# keypad-encoder.net
KiCad netlist of a schematic drawn in EAGLE
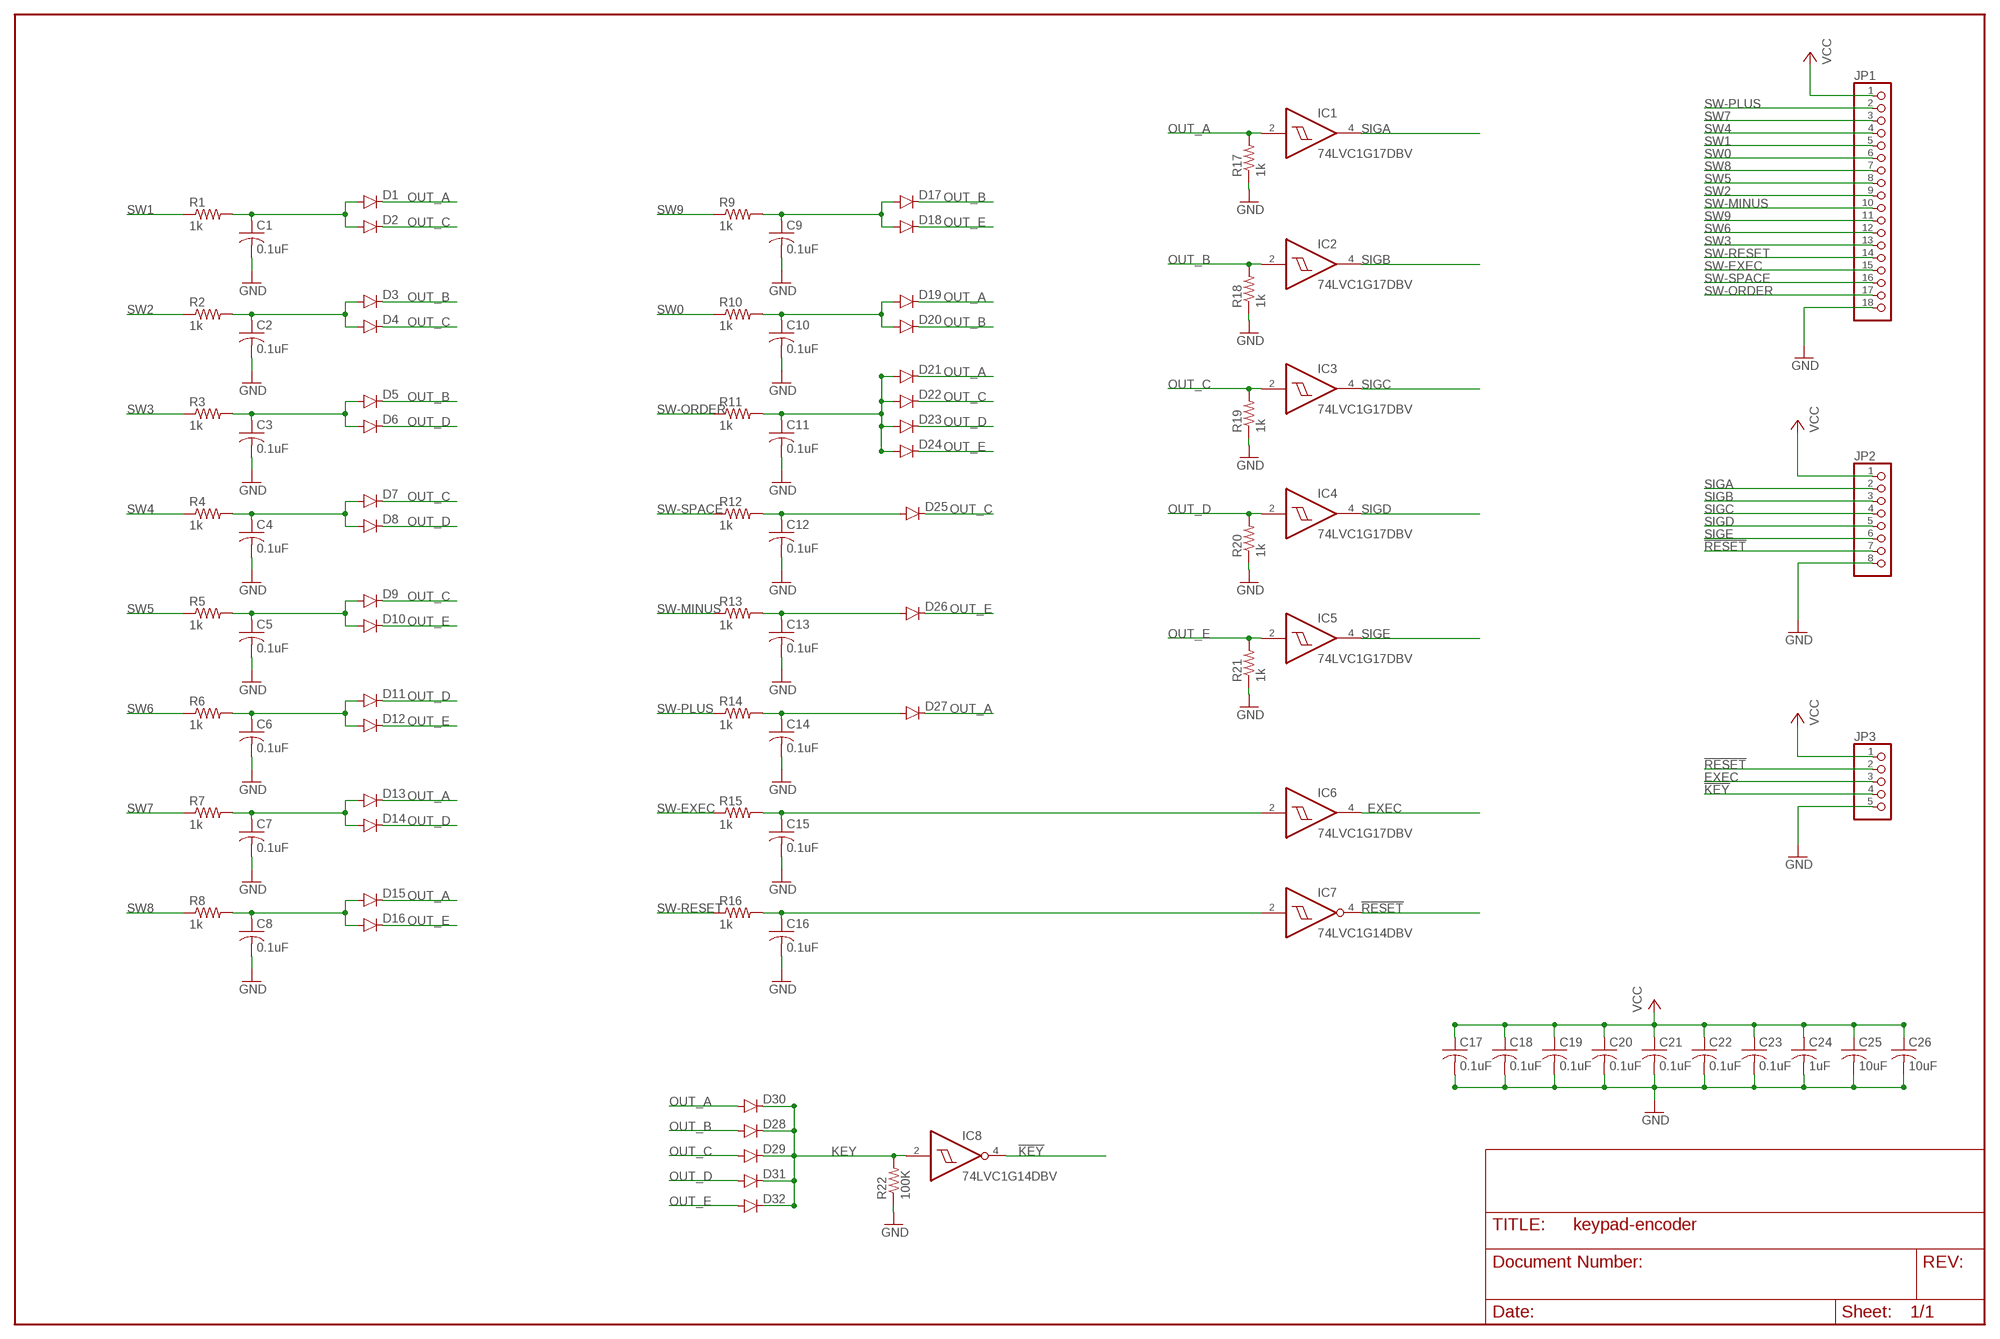
[diagram p0: schematic, sheet 1]

(export (version "E")
  (design (tool "Eeschema 10.0.6"))
  (components
    (comp (ref "C1")
      (value "0.1uF")
      (footprint "eagle-import:C0805")
      (libsource (lib "eagle-import") (part "C-USC0805"))
    )
    (comp (ref "C2")
      (value "0.1uF")
      (footprint "eagle-import:C0805")
      (libsource (lib "eagle-import") (part "C-USC0805"))
    )
    (comp (ref "C3")
      (value "0.1uF")
      (footprint "eagle-import:C0805")
      (libsource (lib "eagle-import") (part "C-USC0805"))
    )
    (comp (ref "C4")
      (value "0.1uF")
      (footprint "eagle-import:C0805")
      (libsource (lib "eagle-import") (part "C-USC0805"))
    )
    (comp (ref "C5")
      (value "0.1uF")
      (footprint "eagle-import:C0805")
      (libsource (lib "eagle-import") (part "C-USC0805"))
    )
    (comp (ref "C6")
      (value "0.1uF")
      (footprint "eagle-import:C0805")
      (libsource (lib "eagle-import") (part "C-USC0805"))
    )
    (comp (ref "C7")
      (value "0.1uF")
      (footprint "eagle-import:C0805")
      (libsource (lib "eagle-import") (part "C-USC0805"))
    )
    (comp (ref "C8")
      (value "0.1uF")
      (footprint "eagle-import:C0805")
      (libsource (lib "eagle-import") (part "C-USC0805"))
    )
    (comp (ref "C9")
      (value "0.1uF")
      (footprint "eagle-import:C0805")
      (libsource (lib "eagle-import") (part "C-USC0805"))
    )
    (comp (ref "C10")
      (value "0.1uF")
      (footprint "eagle-import:C0805")
      (libsource (lib "eagle-import") (part "C-USC0805"))
    )
    (comp (ref "C11")
      (value "0.1uF")
      (footprint "eagle-import:C0805")
      (libsource (lib "eagle-import") (part "C-USC0805"))
    )
    (comp (ref "C12")
      (value "0.1uF")
      (footprint "eagle-import:C0805")
      (libsource (lib "eagle-import") (part "C-USC0805"))
    )
    (comp (ref "C13")
      (value "0.1uF")
      (footprint "eagle-import:C0805")
      (libsource (lib "eagle-import") (part "C-USC0805"))
    )
    (comp (ref "C14")
      (value "0.1uF")
      (footprint "eagle-import:C0805")
      (libsource (lib "eagle-import") (part "C-USC0805"))
    )
    (comp (ref "C15")
      (value "0.1uF")
      (footprint "eagle-import:C0805")
      (libsource (lib "eagle-import") (part "C-USC0805"))
    )
    (comp (ref "C16")
      (value "0.1uF")
      (footprint "eagle-import:C0805")
      (libsource (lib "eagle-import") (part "C-USC0805"))
    )
    (comp (ref "C17")
      (value "0.1uF")
      (footprint "eagle-import:C0805")
      (libsource (lib "eagle-import") (part "C-USC0805"))
    )
    (comp (ref "C18")
      (value "0.1uF")
      (footprint "eagle-import:C0805")
      (libsource (lib "eagle-import") (part "C-USC0805"))
    )
    (comp (ref "C19")
      (value "0.1uF")
      (footprint "eagle-import:C0805")
      (libsource (lib "eagle-import") (part "C-USC0805"))
    )
    (comp (ref "C20")
      (value "0.1uF")
      (footprint "eagle-import:C0805")
      (libsource (lib "eagle-import") (part "C-USC0805"))
    )
    (comp (ref "C21")
      (value "0.1uF")
      (footprint "eagle-import:C0805")
      (libsource (lib "eagle-import") (part "C-USC0805"))
    )
    (comp (ref "C22")
      (value "0.1uF")
      (footprint "eagle-import:C0805")
      (libsource (lib "eagle-import") (part "C-USC0805"))
    )
    (comp (ref "C23")
      (value "0.1uF")
      (footprint "eagle-import:C0805")
      (libsource (lib "eagle-import") (part "C-USC0805"))
    )
    (comp (ref "C24")
      (value "1uF")
      (footprint "eagle-import:C0805")
      (libsource (lib "eagle-import") (part "C-USC0805"))
    )
    (comp (ref "C25")
      (value "10uF")
      (footprint "eagle-import:C0805")
      (libsource (lib "eagle-import") (part "C-USC0805"))
    )
    (comp (ref "C26")
      (value "10uF")
      (footprint "eagle-import:C0805")
      (libsource (lib "eagle-import") (part "C-USC0805"))
    )
    (comp (ref "D1")
      (value "DIODEPTH")
      (footprint "eagle-import:DIODE-1N4001")
      (libsource (lib "eagle-import") (part "DIODEPTH"))
    )
    (comp (ref "D2")
      (value "DIODEPTH")
      (footprint "eagle-import:DIODE-1N4001")
      (libsource (lib "eagle-import") (part "DIODEPTH"))
    )
    (comp (ref "D3")
      (value "DIODEPTH")
      (footprint "eagle-import:DIODE-1N4001")
      (libsource (lib "eagle-import") (part "DIODEPTH"))
    )
    (comp (ref "D4")
      (value "DIODEPTH")
      (footprint "eagle-import:DIODE-1N4001")
      (libsource (lib "eagle-import") (part "DIODEPTH"))
    )
    (comp (ref "D5")
      (value "DIODEPTH")
      (footprint "eagle-import:DIODE-1N4001")
      (libsource (lib "eagle-import") (part "DIODEPTH"))
    )
    (comp (ref "D6")
      (value "DIODEPTH")
      (footprint "eagle-import:DIODE-1N4001")
      (libsource (lib "eagle-import") (part "DIODEPTH"))
    )
    (comp (ref "D7")
      (value "DIODEPTH")
      (footprint "eagle-import:DIODE-1N4001")
      (libsource (lib "eagle-import") (part "DIODEPTH"))
    )
    (comp (ref "D8")
      (value "DIODEPTH")
      (footprint "eagle-import:DIODE-1N4001")
      (libsource (lib "eagle-import") (part "DIODEPTH"))
    )
    (comp (ref "D9")
      (value "DIODEPTH")
      (footprint "eagle-import:DIODE-1N4001")
      (libsource (lib "eagle-import") (part "DIODEPTH"))
    )
    (comp (ref "D10")
      (value "DIODEPTH")
      (footprint "eagle-import:DIODE-1N4001")
      (libsource (lib "eagle-import") (part "DIODEPTH"))
    )
    (comp (ref "D11")
      (value "DIODEPTH")
      (footprint "eagle-import:DIODE-1N4001")
      (libsource (lib "eagle-import") (part "DIODEPTH"))
    )
    (comp (ref "D12")
      (value "DIODEPTH")
      (footprint "eagle-import:DIODE-1N4001")
      (libsource (lib "eagle-import") (part "DIODEPTH"))
    )
    (comp (ref "D13")
      (value "DIODEPTH")
      (footprint "eagle-import:DIODE-1N4001")
      (libsource (lib "eagle-import") (part "DIODEPTH"))
    )
    (comp (ref "D14")
      (value "DIODEPTH")
      (footprint "eagle-import:DIODE-1N4001")
      (libsource (lib "eagle-import") (part "DIODEPTH"))
    )
    (comp (ref "D15")
      (value "DIODEPTH")
      (footprint "eagle-import:DIODE-1N4001")
      (libsource (lib "eagle-import") (part "DIODEPTH"))
    )
    (comp (ref "D16")
      (value "DIODEPTH")
      (footprint "eagle-import:DIODE-1N4001")
      (libsource (lib "eagle-import") (part "DIODEPTH"))
    )
    (comp (ref "D17")
      (value "DIODEPTH")
      (footprint "eagle-import:DIODE-1N4001")
      (libsource (lib "eagle-import") (part "DIODEPTH"))
    )
    (comp (ref "D18")
      (value "DIODEPTH")
      (footprint "eagle-import:DIODE-1N4001")
      (libsource (lib "eagle-import") (part "DIODEPTH"))
    )
    (comp (ref "D19")
      (value "DIODEPTH")
      (footprint "eagle-import:DIODE-1N4001")
      (libsource (lib "eagle-import") (part "DIODEPTH"))
    )
    (comp (ref "D20")
      (value "DIODEPTH")
      (footprint "eagle-import:DIODE-1N4001")
      (libsource (lib "eagle-import") (part "DIODEPTH"))
    )
    (comp (ref "D21")
      (value "DIODEPTH")
      (footprint "eagle-import:DIODE-1N4001")
      (libsource (lib "eagle-import") (part "DIODEPTH"))
    )
    (comp (ref "D22")
      (value "DIODEPTH")
      (footprint "eagle-import:DIODE-1N4001")
      (libsource (lib "eagle-import") (part "DIODEPTH"))
    )
    (comp (ref "D23")
      (value "DIODEPTH")
      (footprint "eagle-import:DIODE-1N4001")
      (libsource (lib "eagle-import") (part "DIODEPTH"))
    )
    (comp (ref "D24")
      (value "DIODEPTH")
      (footprint "eagle-import:DIODE-1N4001")
      (libsource (lib "eagle-import") (part "DIODEPTH"))
    )
    (comp (ref "D25")
      (value "DIODEPTH")
      (footprint "eagle-import:DIODE-1N4001")
      (libsource (lib "eagle-import") (part "DIODEPTH"))
    )
    (comp (ref "D26")
      (value "DIODEPTH")
      (footprint "eagle-import:DIODE-1N4001")
      (libsource (lib "eagle-import") (part "DIODEPTH"))
    )
    (comp (ref "D27")
      (value "DIODEPTH")
      (footprint "eagle-import:DIODE-1N4001")
      (libsource (lib "eagle-import") (part "DIODEPTH"))
    )
    (comp (ref "D28")
      (value "DIODEPTH")
      (footprint "eagle-import:DIODE-1N4001")
      (libsource (lib "eagle-import") (part "DIODEPTH"))
    )
    (comp (ref "D29")
      (value "DIODEPTH")
      (footprint "eagle-import:DIODE-1N4001")
      (libsource (lib "eagle-import") (part "DIODEPTH"))
    )
    (comp (ref "D30")
      (value "DIODEPTH")
      (footprint "eagle-import:DIODE-1N4001")
      (libsource (lib "eagle-import") (part "DIODEPTH"))
    )
    (comp (ref "D31")
      (value "DIODEPTH")
      (footprint "eagle-import:DIODE-1N4001")
      (libsource (lib "eagle-import") (part "DIODEPTH"))
    )
    (comp (ref "D32")
      (value "DIODEPTH")
      (footprint "eagle-import:DIODE-1N4001")
      (libsource (lib "eagle-import") (part "DIODEPTH"))
    )
    (comp (ref "IC1")
      (value "74LVC1G17DBV")
      (footprint "eagle-import:SOT23-5")
      (libsource (lib "eagle-import") (part "741G17DBVLVC"))
    )
    (comp (ref "IC2")
      (value "74LVC1G17DBV")
      (footprint "eagle-import:SOT23-5")
      (libsource (lib "eagle-import") (part "741G17DBVLVC"))
    )
    (comp (ref "IC3")
      (value "74LVC1G17DBV")
      (footprint "eagle-import:SOT23-5")
      (libsource (lib "eagle-import") (part "741G17DBVLVC"))
    )
    (comp (ref "IC4")
      (value "74LVC1G17DBV")
      (footprint "eagle-import:SOT23-5")
      (libsource (lib "eagle-import") (part "741G17DBVLVC"))
    )
    (comp (ref "IC5")
      (value "74LVC1G17DBV")
      (footprint "eagle-import:SOT23-5")
      (libsource (lib "eagle-import") (part "741G17DBVLVC"))
    )
    (comp (ref "IC6")
      (value "74LVC1G17DBV")
      (footprint "eagle-import:SOT23-5")
      (libsource (lib "eagle-import") (part "741G17DBVLVC"))
    )
    (comp (ref "IC7")
      (value "74LVC1G14DBV")
      (footprint "eagle-import:SOT23-5")
      (libsource (lib "eagle-import") (part "741G14DBVLVC"))
    )
    (comp (ref "IC8")
      (value "74LVC1G14DBV")
      (footprint "eagle-import:SOT23-5")
      (libsource (lib "eagle-import") (part "741G14DBVLVC"))
    )
    (comp (ref "JP1")
      (value "PINHD-1X18")
      (footprint "eagle-import:1X18")
      (libsource (lib "eagle-import") (part "PINHD-1X18"))
    )
    (comp (ref "JP2")
      (value "PINHD-1X8")
      (footprint "eagle-import:1X08")
      (libsource (lib "eagle-import") (part "PINHD-1X8"))
    )
    (comp (ref "JP3")
      (value "PINHD-1X5")
      (footprint "eagle-import:1X05")
      (libsource (lib "eagle-import") (part "PINHD-1X5"))
    )
    (comp (ref "R1")
      (value "1k")
      (footprint "eagle-import:R0805")
      (libsource (lib "eagle-import") (part "R-US_R0805"))
    )
    (comp (ref "R2")
      (value "1k")
      (footprint "eagle-import:R0805")
      (libsource (lib "eagle-import") (part "R-US_R0805"))
    )
    (comp (ref "R3")
      (value "1k")
      (footprint "eagle-import:R0805")
      (libsource (lib "eagle-import") (part "R-US_R0805"))
    )
    (comp (ref "R4")
      (value "1k")
      (footprint "eagle-import:R0805")
      (libsource (lib "eagle-import") (part "R-US_R0805"))
    )
    (comp (ref "R5")
      (value "1k")
      (footprint "eagle-import:R0805")
      (libsource (lib "eagle-import") (part "R-US_R0805"))
    )
    (comp (ref "R6")
      (value "1k")
      (footprint "eagle-import:R0805")
      (libsource (lib "eagle-import") (part "R-US_R0805"))
    )
    (comp (ref "R7")
      (value "1k")
      (footprint "eagle-import:R0805")
      (libsource (lib "eagle-import") (part "R-US_R0805"))
    )
    (comp (ref "R8")
      (value "1k")
      (footprint "eagle-import:R0805")
      (libsource (lib "eagle-import") (part "R-US_R0805"))
    )
    (comp (ref "R9")
      (value "1k")
      (footprint "eagle-import:R0805")
      (libsource (lib "eagle-import") (part "R-US_R0805"))
    )
    (comp (ref "R10")
      (value "1k")
      (footprint "eagle-import:R0805")
      (libsource (lib "eagle-import") (part "R-US_R0805"))
    )
    (comp (ref "R11")
      (value "1k")
      (footprint "eagle-import:R0805")
      (libsource (lib "eagle-import") (part "R-US_R0805"))
    )
    (comp (ref "R12")
      (value "1k")
      (footprint "eagle-import:R0805")
      (libsource (lib "eagle-import") (part "R-US_R0805"))
    )
    (comp (ref "R13")
      (value "1k")
      (footprint "eagle-import:R0805")
      (libsource (lib "eagle-import") (part "R-US_R0805"))
    )
    (comp (ref "R14")
      (value "1k")
      (footprint "eagle-import:R0805")
      (libsource (lib "eagle-import") (part "R-US_R0805"))
    )
    (comp (ref "R15")
      (value "1k")
      (footprint "eagle-import:R0805")
      (libsource (lib "eagle-import") (part "R-US_R0805"))
    )
    (comp (ref "R16")
      (value "1k")
      (footprint "eagle-import:R0805")
      (libsource (lib "eagle-import") (part "R-US_R0805"))
    )
    (comp (ref "R17")
      (value "1k")
      (footprint "eagle-import:R0805")
      (libsource (lib "eagle-import") (part "R-US_R0805"))
    )
    (comp (ref "R18")
      (value "1k")
      (footprint "eagle-import:R0805")
      (libsource (lib "eagle-import") (part "R-US_R0805"))
    )
    (comp (ref "R19")
      (value "1k")
      (footprint "eagle-import:R0805")
      (libsource (lib "eagle-import") (part "R-US_R0805"))
    )
    (comp (ref "R20")
      (value "1k")
      (footprint "eagle-import:R0805")
      (libsource (lib "eagle-import") (part "R-US_R0805"))
    )
    (comp (ref "R21")
      (value "1k")
      (footprint "eagle-import:R0805")
      (libsource (lib "eagle-import") (part "R-US_R0805"))
    )
    (comp (ref "R22")
      (value "100K")
      (footprint "eagle-import:R0805")
      (libsource (lib "eagle-import") (part "R-US_R0805"))
    )
  )
  (nets
    (net (code "1") (name "/EXEC") (class "Default")
      (node (ref "IC6") (pin "4") (pinfunction "O_4") (pintype "output"))
      (node (ref "JP3") (pin "3") (pinfunction "3_3") (pintype "passive"))
    )
    (net (code "2") (name "/KEY") (class "Default")
      (node (ref "D28") (pin "C") (pinfunction "C_C") (pintype "passive"))
      (node (ref "D29") (pin "C") (pinfunction "C_C") (pintype "passive"))
      (node (ref "D30") (pin "C") (pinfunction "C_C") (pintype "passive"))
      (node (ref "D31") (pin "C") (pinfunction "C_C") (pintype "passive"))
      (node (ref "D32") (pin "C") (pinfunction "C_C") (pintype "passive"))
      (node (ref "IC8") (pin "2") (pinfunction "I_2") (pintype "input"))
      (node (ref "R22") (pin "2") (pinfunction "2_2") (pintype "passive"))
    )
    (net (code "3") (name "/OUT_A") (class "Default")
      (node (ref "D1") (pin "C") (pinfunction "C_C") (pintype "passive"))
      (node (ref "D13") (pin "C") (pinfunction "C_C") (pintype "passive"))
      (node (ref "D15") (pin "C") (pinfunction "C_C") (pintype "passive"))
      (node (ref "D19") (pin "C") (pinfunction "C_C") (pintype "passive"))
      (node (ref "D21") (pin "C") (pinfunction "C_C") (pintype "passive"))
      (node (ref "D27") (pin "C") (pinfunction "C_C") (pintype "passive"))
      (node (ref "D30") (pin "A") (pinfunction "A_A") (pintype "passive"))
      (node (ref "IC1") (pin "2") (pinfunction "I_2") (pintype "input"))
      (node (ref "R17") (pin "2") (pinfunction "2_2") (pintype "passive"))
    )
    (net (code "4") (name "/OUT_B") (class "Default")
      (node (ref "D17") (pin "C") (pinfunction "C_C") (pintype "passive"))
      (node (ref "D20") (pin "C") (pinfunction "C_C") (pintype "passive"))
      (node (ref "D28") (pin "A") (pinfunction "A_A") (pintype "passive"))
      (node (ref "D3") (pin "C") (pinfunction "C_C") (pintype "passive"))
      (node (ref "D5") (pin "C") (pinfunction "C_C") (pintype "passive"))
      (node (ref "IC2") (pin "2") (pinfunction "I_2") (pintype "input"))
      (node (ref "R18") (pin "2") (pinfunction "2_2") (pintype "passive"))
    )
    (net (code "5") (name "/OUT_C") (class "Default")
      (node (ref "D2") (pin "C") (pinfunction "C_C") (pintype "passive"))
      (node (ref "D22") (pin "C") (pinfunction "C_C") (pintype "passive"))
      (node (ref "D25") (pin "C") (pinfunction "C_C") (pintype "passive"))
      (node (ref "D29") (pin "A") (pinfunction "A_A") (pintype "passive"))
      (node (ref "D4") (pin "C") (pinfunction "C_C") (pintype "passive"))
      (node (ref "D7") (pin "C") (pinfunction "C_C") (pintype "passive"))
      (node (ref "D9") (pin "C") (pinfunction "C_C") (pintype "passive"))
      (node (ref "IC3") (pin "2") (pinfunction "I_2") (pintype "input"))
      (node (ref "R19") (pin "2") (pinfunction "2_2") (pintype "passive"))
    )
    (net (code "6") (name "/OUT_D") (class "Default")
      (node (ref "D11") (pin "C") (pinfunction "C_C") (pintype "passive"))
      (node (ref "D14") (pin "C") (pinfunction "C_C") (pintype "passive"))
      (node (ref "D23") (pin "C") (pinfunction "C_C") (pintype "passive"))
      (node (ref "D31") (pin "A") (pinfunction "A_A") (pintype "passive"))
      (node (ref "D6") (pin "C") (pinfunction "C_C") (pintype "passive"))
      (node (ref "D8") (pin "C") (pinfunction "C_C") (pintype "passive"))
      (node (ref "IC4") (pin "2") (pinfunction "I_2") (pintype "input"))
      (node (ref "R20") (pin "2") (pinfunction "2_2") (pintype "passive"))
    )
    (net (code "7") (name "/OUT_E") (class "Default")
      (node (ref "D10") (pin "C") (pinfunction "C_C") (pintype "passive"))
      (node (ref "D12") (pin "C") (pinfunction "C_C") (pintype "passive"))
      (node (ref "D16") (pin "C") (pinfunction "C_C") (pintype "passive"))
      (node (ref "D18") (pin "C") (pinfunction "C_C") (pintype "passive"))
      (node (ref "D24") (pin "C") (pinfunction "C_C") (pintype "passive"))
      (node (ref "D26") (pin "C") (pinfunction "C_C") (pintype "passive"))
      (node (ref "D32") (pin "A") (pinfunction "A_A") (pintype "passive"))
      (node (ref "IC5") (pin "2") (pinfunction "I_2") (pintype "input"))
      (node (ref "R21") (pin "2") (pinfunction "2_2") (pintype "passive"))
    )
    (net (code "8") (name "/SIGA") (class "Default")
      (node (ref "IC1") (pin "4") (pinfunction "O_4") (pintype "output"))
      (node (ref "JP2") (pin "2") (pinfunction "2_2") (pintype "passive"))
    )
    (net (code "9") (name "/SIGB") (class "Default")
      (node (ref "IC2") (pin "4") (pinfunction "O_4") (pintype "output"))
      (node (ref "JP2") (pin "3") (pinfunction "3_3") (pintype "passive"))
    )
    (net (code "10") (name "/SIGC") (class "Default")
      (node (ref "IC3") (pin "4") (pinfunction "O_4") (pintype "output"))
      (node (ref "JP2") (pin "4") (pinfunction "4_4") (pintype "passive"))
    )
    (net (code "11") (name "/SIGD") (class "Default")
      (node (ref "IC4") (pin "4") (pinfunction "O_4") (pintype "output"))
      (node (ref "JP2") (pin "5") (pinfunction "5_5") (pintype "passive"))
    )
    (net (code "12") (name "/SIGE") (class "Default")
      (node (ref "IC5") (pin "4") (pinfunction "O_4") (pintype "output"))
      (node (ref "JP2") (pin "6") (pinfunction "6_6") (pintype "passive"))
    )
    (net (code "13") (name "/SW-EXEC") (class "Default")
      (node (ref "JP1") (pin "15") (pinfunction "15_15") (pintype "passive"))
      (node (ref "R15") (pin "1") (pinfunction "1_1") (pintype "passive"))
    )
    (net (code "14") (name "/SW-MINUS") (class "Default")
      (node (ref "JP1") (pin "10") (pinfunction "10_10") (pintype "passive"))
      (node (ref "R13") (pin "1") (pinfunction "1_1") (pintype "passive"))
    )
    (net (code "15") (name "/SW-ORDER") (class "Default")
      (node (ref "JP1") (pin "17") (pinfunction "17_17") (pintype "passive"))
      (node (ref "R11") (pin "1") (pinfunction "1_1") (pintype "passive"))
    )
    (net (code "16") (name "/SW-PLUS") (class "Default")
      (node (ref "JP1") (pin "2") (pinfunction "2_2") (pintype "passive"))
      (node (ref "R14") (pin "1") (pinfunction "1_1") (pintype "passive"))
    )
    (net (code "17") (name "/SW-RESET") (class "Default")
      (node (ref "JP1") (pin "14") (pinfunction "14_14") (pintype "passive"))
      (node (ref "R16") (pin "1") (pinfunction "1_1") (pintype "passive"))
    )
    (net (code "18") (name "/SW-SPACE") (class "Default")
      (node (ref "JP1") (pin "16") (pinfunction "16_16") (pintype "passive"))
      (node (ref "R12") (pin "1") (pinfunction "1_1") (pintype "passive"))
    )
    (net (code "19") (name "/SW0") (class "Default")
      (node (ref "JP1") (pin "6") (pinfunction "6_6") (pintype "passive"))
      (node (ref "R10") (pin "1") (pinfunction "1_1") (pintype "passive"))
    )
    (net (code "20") (name "/SW1") (class "Default")
      (node (ref "JP1") (pin "5") (pinfunction "5_5") (pintype "passive"))
      (node (ref "R1") (pin "1") (pinfunction "1_1") (pintype "passive"))
    )
    (net (code "21") (name "/SW2") (class "Default")
      (node (ref "JP1") (pin "9") (pinfunction "9_9") (pintype "passive"))
      (node (ref "R2") (pin "1") (pinfunction "1_1") (pintype "passive"))
    )
    (net (code "22") (name "/SW3") (class "Default")
      (node (ref "JP1") (pin "13") (pinfunction "13_13") (pintype "passive"))
      (node (ref "R3") (pin "1") (pinfunction "1_1") (pintype "passive"))
    )
    (net (code "23") (name "/SW4") (class "Default")
      (node (ref "JP1") (pin "4") (pinfunction "4_4") (pintype "passive"))
      (node (ref "R4") (pin "1") (pinfunction "1_1") (pintype "passive"))
    )
    (net (code "24") (name "/SW5") (class "Default")
      (node (ref "JP1") (pin "8") (pinfunction "8_8") (pintype "passive"))
      (node (ref "R5") (pin "1") (pinfunction "1_1") (pintype "passive"))
    )
    (net (code "25") (name "/SW6") (class "Default")
      (node (ref "JP1") (pin "12") (pinfunction "12_12") (pintype "passive"))
      (node (ref "R6") (pin "1") (pinfunction "1_1") (pintype "passive"))
    )
    (net (code "26") (name "/SW7") (class "Default")
      (node (ref "JP1") (pin "3") (pinfunction "3_3") (pintype "passive"))
      (node (ref "R7") (pin "1") (pinfunction "1_1") (pintype "passive"))
    )
    (net (code "27") (name "/SW8") (class "Default")
      (node (ref "JP1") (pin "7") (pinfunction "7_7") (pintype "passive"))
      (node (ref "R8") (pin "1") (pinfunction "1_1") (pintype "passive"))
    )
    (net (code "28") (name "/SW9") (class "Default")
      (node (ref "JP1") (pin "11") (pinfunction "11_11") (pintype "passive"))
      (node (ref "R9") (pin "1") (pinfunction "1_1") (pintype "passive"))
    )
    (net (code "29") (name "/~{KEY}") (class "Default")
      (node (ref "IC8") (pin "4") (pinfunction "O_4") (pintype "output"))
      (node (ref "JP3") (pin "4") (pinfunction "4_4") (pintype "passive"))
    )
    (net (code "30") (name "/~{RESET}") (class "Default")
      (node (ref "IC7") (pin "4") (pinfunction "O_4") (pintype "output"))
      (node (ref "JP2") (pin "7") (pinfunction "7_7") (pintype "passive"))
      (node (ref "JP3") (pin "2") (pinfunction "2_2") (pintype "passive"))
    )
    (net (code "31") (name "GND") (class "Default")
      (node (ref "C1") (pin "2") (pinfunction "2_2") (pintype "passive"))
      (node (ref "C10") (pin "2") (pinfunction "2_2") (pintype "passive"))
      (node (ref "C11") (pin "2") (pinfunction "2_2") (pintype "passive"))
      (node (ref "C12") (pin "2") (pinfunction "2_2") (pintype "passive"))
      (node (ref "C13") (pin "2") (pinfunction "2_2") (pintype "passive"))
      (node (ref "C14") (pin "2") (pinfunction "2_2") (pintype "passive"))
      (node (ref "C15") (pin "2") (pinfunction "2_2") (pintype "passive"))
      (node (ref "C16") (pin "2") (pinfunction "2_2") (pintype "passive"))
      (node (ref "C17") (pin "2") (pinfunction "2_2") (pintype "passive"))
      (node (ref "C18") (pin "2") (pinfunction "2_2") (pintype "passive"))
      (node (ref "C19") (pin "2") (pinfunction "2_2") (pintype "passive"))
      (node (ref "C2") (pin "2") (pinfunction "2_2") (pintype "passive"))
      (node (ref "C20") (pin "2") (pinfunction "2_2") (pintype "passive"))
      (node (ref "C21") (pin "2") (pinfunction "2_2") (pintype "passive"))
      (node (ref "C22") (pin "2") (pinfunction "2_2") (pintype "passive"))
      (node (ref "C23") (pin "2") (pinfunction "2_2") (pintype "passive"))
      (node (ref "C24") (pin "2") (pinfunction "2_2") (pintype "passive"))
      (node (ref "C25") (pin "2") (pinfunction "2_2") (pintype "passive"))
      (node (ref "C26") (pin "2") (pinfunction "2_2") (pintype "passive"))
      (node (ref "C3") (pin "2") (pinfunction "2_2") (pintype "passive"))
      (node (ref "C4") (pin "2") (pinfunction "2_2") (pintype "passive"))
      (node (ref "C5") (pin "2") (pinfunction "2_2") (pintype "passive"))
      (node (ref "C6") (pin "2") (pinfunction "2_2") (pintype "passive"))
      (node (ref "C7") (pin "2") (pinfunction "2_2") (pintype "passive"))
      (node (ref "C8") (pin "2") (pinfunction "2_2") (pintype "passive"))
      (node (ref "C9") (pin "2") (pinfunction "2_2") (pintype "passive"))
      (node (ref "JP1") (pin "18") (pinfunction "18_18") (pintype "passive"))
      (node (ref "JP2") (pin "8") (pinfunction "8_8") (pintype "passive"))
      (node (ref "JP3") (pin "5") (pinfunction "5_5") (pintype "passive"))
      (node (ref "R17") (pin "1") (pinfunction "1_1") (pintype "passive"))
      (node (ref "R18") (pin "1") (pinfunction "1_1") (pintype "passive"))
      (node (ref "R19") (pin "1") (pinfunction "1_1") (pintype "passive"))
      (node (ref "R20") (pin "1") (pinfunction "1_1") (pintype "passive"))
      (node (ref "R21") (pin "1") (pinfunction "1_1") (pintype "passive"))
      (node (ref "R22") (pin "1") (pinfunction "1_1") (pintype "passive"))
    )
    (net (code "32") (name "Net-(C1-Pad1)") (class "Default")
      (node (ref "C1") (pin "1") (pinfunction "1_1") (pintype "passive"))
      (node (ref "D1") (pin "A") (pinfunction "A_A") (pintype "passive"))
      (node (ref "D2") (pin "A") (pinfunction "A_A") (pintype "passive"))
      (node (ref "R1") (pin "2") (pinfunction "2_2") (pintype "passive"))
    )
    (net (code "33") (name "Net-(C2-Pad1)") (class "Default")
      (node (ref "C2") (pin "1") (pinfunction "1_1") (pintype "passive"))
      (node (ref "D3") (pin "A") (pinfunction "A_A") (pintype "passive"))
      (node (ref "D4") (pin "A") (pinfunction "A_A") (pintype "passive"))
      (node (ref "R2") (pin "2") (pinfunction "2_2") (pintype "passive"))
    )
    (net (code "34") (name "Net-(C3-Pad1)") (class "Default")
      (node (ref "C3") (pin "1") (pinfunction "1_1") (pintype "passive"))
      (node (ref "D5") (pin "A") (pinfunction "A_A") (pintype "passive"))
      (node (ref "D6") (pin "A") (pinfunction "A_A") (pintype "passive"))
      (node (ref "R3") (pin "2") (pinfunction "2_2") (pintype "passive"))
    )
    (net (code "35") (name "Net-(C4-Pad1)") (class "Default")
      (node (ref "C4") (pin "1") (pinfunction "1_1") (pintype "passive"))
      (node (ref "D7") (pin "A") (pinfunction "A_A") (pintype "passive"))
      (node (ref "D8") (pin "A") (pinfunction "A_A") (pintype "passive"))
      (node (ref "R4") (pin "2") (pinfunction "2_2") (pintype "passive"))
    )
    (net (code "36") (name "Net-(C5-Pad1)") (class "Default")
      (node (ref "C5") (pin "1") (pinfunction "1_1") (pintype "passive"))
      (node (ref "D10") (pin "A") (pinfunction "A_A") (pintype "passive"))
      (node (ref "D9") (pin "A") (pinfunction "A_A") (pintype "passive"))
      (node (ref "R5") (pin "2") (pinfunction "2_2") (pintype "passive"))
    )
    (net (code "37") (name "Net-(C6-Pad1)") (class "Default")
      (node (ref "C6") (pin "1") (pinfunction "1_1") (pintype "passive"))
      (node (ref "D11") (pin "A") (pinfunction "A_A") (pintype "passive"))
      (node (ref "D12") (pin "A") (pinfunction "A_A") (pintype "passive"))
      (node (ref "R6") (pin "2") (pinfunction "2_2") (pintype "passive"))
    )
    (net (code "38") (name "Net-(C7-Pad1)") (class "Default")
      (node (ref "C7") (pin "1") (pinfunction "1_1") (pintype "passive"))
      (node (ref "D13") (pin "A") (pinfunction "A_A") (pintype "passive"))
      (node (ref "D14") (pin "A") (pinfunction "A_A") (pintype "passive"))
      (node (ref "R7") (pin "2") (pinfunction "2_2") (pintype "passive"))
    )
    (net (code "39") (name "Net-(C8-Pad1)") (class "Default")
      (node (ref "C8") (pin "1") (pinfunction "1_1") (pintype "passive"))
      (node (ref "D15") (pin "A") (pinfunction "A_A") (pintype "passive"))
      (node (ref "D16") (pin "A") (pinfunction "A_A") (pintype "passive"))
      (node (ref "R8") (pin "2") (pinfunction "2_2") (pintype "passive"))
    )
    (net (code "40") (name "Net-(C9-Pad1)") (class "Default")
      (node (ref "C9") (pin "1") (pinfunction "1_1") (pintype "passive"))
      (node (ref "D17") (pin "A") (pinfunction "A_A") (pintype "passive"))
      (node (ref "D18") (pin "A") (pinfunction "A_A") (pintype "passive"))
      (node (ref "R9") (pin "2") (pinfunction "2_2") (pintype "passive"))
    )
    (net (code "41") (name "Net-(C10-Pad1)") (class "Default")
      (node (ref "C10") (pin "1") (pinfunction "1_1") (pintype "passive"))
      (node (ref "D19") (pin "A") (pinfunction "A_A") (pintype "passive"))
      (node (ref "D20") (pin "A") (pinfunction "A_A") (pintype "passive"))
      (node (ref "R10") (pin "2") (pinfunction "2_2") (pintype "passive"))
    )
    (net (code "42") (name "Net-(C11-Pad1)") (class "Default")
      (node (ref "C11") (pin "1") (pinfunction "1_1") (pintype "passive"))
      (node (ref "D21") (pin "A") (pinfunction "A_A") (pintype "passive"))
      (node (ref "D22") (pin "A") (pinfunction "A_A") (pintype "passive"))
      (node (ref "D23") (pin "A") (pinfunction "A_A") (pintype "passive"))
      (node (ref "D24") (pin "A") (pinfunction "A_A") (pintype "passive"))
      (node (ref "R11") (pin "2") (pinfunction "2_2") (pintype "passive"))
    )
    (net (code "43") (name "Net-(C12-Pad1)") (class "Default")
      (node (ref "C12") (pin "1") (pinfunction "1_1") (pintype "passive"))
      (node (ref "D25") (pin "A") (pinfunction "A_A") (pintype "passive"))
      (node (ref "R12") (pin "2") (pinfunction "2_2") (pintype "passive"))
    )
    (net (code "44") (name "Net-(C13-Pad1)") (class "Default")
      (node (ref "C13") (pin "1") (pinfunction "1_1") (pintype "passive"))
      (node (ref "D26") (pin "A") (pinfunction "A_A") (pintype "passive"))
      (node (ref "R13") (pin "2") (pinfunction "2_2") (pintype "passive"))
    )
    (net (code "45") (name "Net-(C14-Pad1)") (class "Default")
      (node (ref "C14") (pin "1") (pinfunction "1_1") (pintype "passive"))
      (node (ref "D27") (pin "A") (pinfunction "A_A") (pintype "passive"))
      (node (ref "R14") (pin "2") (pinfunction "2_2") (pintype "passive"))
    )
    (net (code "46") (name "Net-(IC6A-I)") (class "Default")
      (node (ref "C15") (pin "1") (pinfunction "1_1") (pintype "passive"))
      (node (ref "IC6") (pin "2") (pinfunction "I_2") (pintype "input"))
      (node (ref "R15") (pin "2") (pinfunction "2_2") (pintype "passive"))
    )
    (net (code "47") (name "Net-(IC7A-I)") (class "Default")
      (node (ref "C16") (pin "1") (pinfunction "1_1") (pintype "passive"))
      (node (ref "IC7") (pin "2") (pinfunction "I_2") (pintype "input"))
      (node (ref "R16") (pin "2") (pinfunction "2_2") (pintype "passive"))
    )
    (net (code "48") (name "VCC") (class "Default")
      (node (ref "C17") (pin "1") (pinfunction "1_1") (pintype "passive"))
      (node (ref "C18") (pin "1") (pinfunction "1_1") (pintype "passive"))
      (node (ref "C19") (pin "1") (pinfunction "1_1") (pintype "passive"))
      (node (ref "C20") (pin "1") (pinfunction "1_1") (pintype "passive"))
      (node (ref "C21") (pin "1") (pinfunction "1_1") (pintype "passive"))
      (node (ref "C22") (pin "1") (pinfunction "1_1") (pintype "passive"))
      (node (ref "C23") (pin "1") (pinfunction "1_1") (pintype "passive"))
      (node (ref "C24") (pin "1") (pinfunction "1_1") (pintype "passive"))
      (node (ref "C25") (pin "1") (pinfunction "1_1") (pintype "passive"))
      (node (ref "C26") (pin "1") (pinfunction "1_1") (pintype "passive"))
      (node (ref "JP1") (pin "1") (pinfunction "1_1") (pintype "passive"))
      (node (ref "JP2") (pin "1") (pinfunction "1_1") (pintype "passive"))
      (node (ref "JP3") (pin "1") (pinfunction "1_1") (pintype "passive"))
    )
  )
)
